# Control.net
KiCad netlist of a schematic drawn in Altium Designer
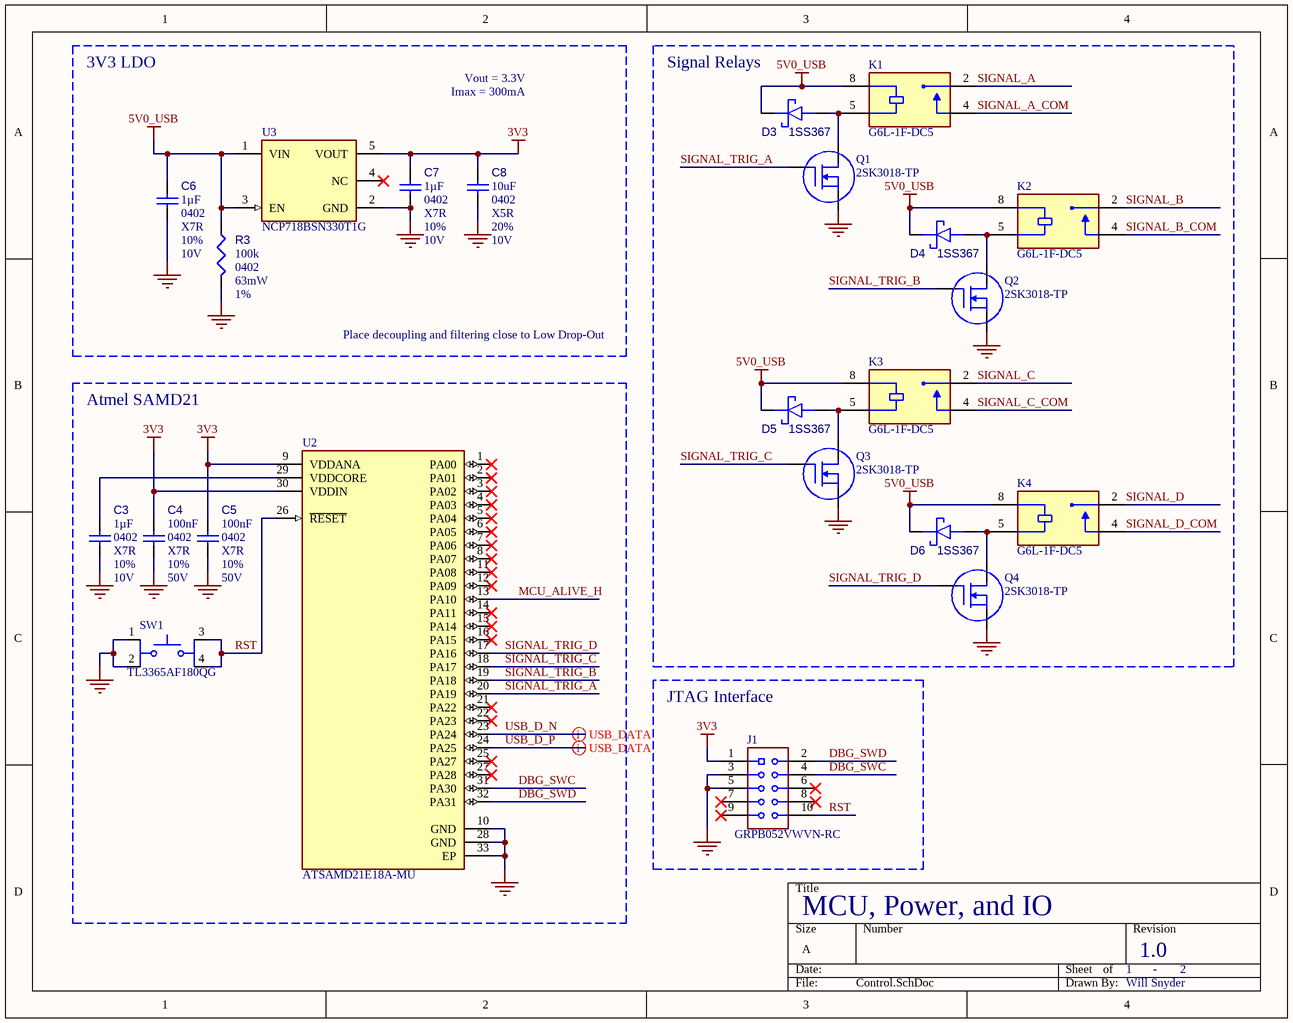
[diagram p0: Control.SchDoc]

(export (version "E")
  (design (tool "Eeschema 10.0.6"))
  (components
    (comp (ref "C3")
      (value "1µF")
      (footprint "CAPC1005X55X30NL05T10")
      (fields
        (field (name "CASE/PACKAGE") "0402")
        (field (name "VOLTAGE RATING") "10V")
        (field (name "CAPACITOR TYPE") "X7R")
        (field (name "TOLERANCE") "10%")
        (field (name "Comment") "GRM155Z71A105KE01D")
      )
      (libsource (lib "Personal Workspace") (part "CAP-NP-2"))
    )
    (comp (ref "C4")
      (value "100nF")
      (footprint "CAPC1005X55X30NL05T10")
      (fields
        (field (name "VOLTAGE RATING") "50V")
        (field (name "CAPACITOR TYPE") "X7R")
        (field (name "CASE/PACKAGE") "0402")
        (field (name "TOLERANCE") "10%")
        (field (name "Comment") "04025C104KAT4A")
      )
      (libsource (lib "Personal Workspace") (part "CAP-NP-2"))
    )
    (comp (ref "C5")
      (value "100nF")
      (footprint "CAPC1005X55X30NL05T10")
      (fields
        (field (name "VOLTAGE RATING") "50V")
        (field (name "CAPACITOR TYPE") "X7R")
        (field (name "CASE/PACKAGE") "0402")
        (field (name "TOLERANCE") "10%")
        (field (name "Comment") "04025C104KAT4A")
      )
      (libsource (lib "Personal Workspace") (part "CAP-NP-2"))
    )
    (comp (ref "C6")
      (value "1µF")
      (footprint "CAPC1005X55X30NL05T10")
      (fields
        (field (name "CASE/PACKAGE") "0402")
        (field (name "VOLTAGE RATING") "10V")
        (field (name "CAPACITOR TYPE") "X7R")
        (field (name "TOLERANCE") "10%")
        (field (name "Comment") "GRM155Z71A105KE01D")
      )
      (libsource (lib "Personal Workspace") (part "CAP-NP-2"))
    )
    (comp (ref "C7")
      (value "1µF")
      (footprint "CAPC1005X55X30NL05T10")
      (fields
        (field (name "CASE/PACKAGE") "0402")
        (field (name "VOLTAGE RATING") "10V")
        (field (name "CAPACITOR TYPE") "X7R")
        (field (name "TOLERANCE") "10%")
        (field (name "Comment") "GRM155Z71A105KE01D")
      )
      (libsource (lib "Personal Workspace") (part "CAP-NP-2"))
    )
    (comp (ref "C8")
      (value "10uF")
      (footprint "CAPC1005X55X30NL05T10")
      (fields
        (field (name "CAPACITOR TYPE") "X5R")
        (field (name "VOLTAGE RATING") "10V")
        (field (name "TOLERANCE") "20%")
        (field (name "CASE/PACKAGE") "0402")
        (field (name "Comment") "GRM155R61A106ME11J")
      )
      (libsource (lib "Personal Workspace") (part "CAP-NP-2"))
    )
    (comp (ref "D3")
      (value "1SS367")
      (footprint "SOD2513X114N")
      (description "Diode Schottky 10V 100mA USC")
      (libsource (lib "Personal Workspace") (part "1SS367"))
    )
    (comp (ref "D4")
      (value "1SS367")
      (footprint "SOD2513X114N")
      (description "Diode Schottky 10V 100mA USC")
      (libsource (lib "Personal Workspace") (part "1SS367"))
    )
    (comp (ref "D5")
      (value "1SS367")
      (footprint "SOD2513X114N")
      (description "Diode Schottky 10V 100mA USC")
      (libsource (lib "Personal Workspace") (part "1SS367"))
    )
    (comp (ref "D6")
      (value "1SS367")
      (footprint "SOD2513X114N")
      (description "Diode Schottky 10V 100mA USC")
      (libsource (lib "Personal Workspace") (part "1SS367"))
    )
    (comp (ref "J1")
      (value "GRPB052VWVN-RC")
      (footprint "SULLINS_GRPB052VWVN-RC")
      (description "Connector Header Through Hole 10 position 0.050 (1.27mm)")
      (fields (field (name "MF") "Sullins"))
      (libsource (lib "Personal Workspace") (part "GRPB052VWVN-RC"))
    )
    (comp (ref "K1")
      (value "G6L-1F-DC5")
      (footprint "RELAY_G6L-1F-DC5")
      (description "Telecom Relay SPST-NO (1 Form A) Surface Mount")
      (fields (field (name "MP") "G6L-1F-TR-DC5") (field (name "MF") "Omron Electronics"))
      (libsource (lib "Personal Workspace") (part "G6L-1F-DC5"))
    )
    (comp (ref "K2")
      (value "G6L-1F-DC5")
      (footprint "RELAY_G6L-1F-DC5")
      (description "Telecom Relay SPST-NO (1 Form A) Surface Mount")
      (fields (field (name "MP") "G6L-1F-TR-DC5") (field (name "MF") "Omron Electronics"))
      (libsource (lib "Personal Workspace") (part "G6L-1F-DC5"))
    )
    (comp (ref "K3")
      (value "G6L-1F-DC5")
      (footprint "RELAY_G6L-1F-DC5")
      (description "Telecom Relay SPST-NO (1 Form A) Surface Mount")
      (fields (field (name "MP") "G6L-1F-TR-DC5") (field (name "MF") "Omron Electronics"))
      (libsource (lib "Personal Workspace") (part "G6L-1F-DC5"))
    )
    (comp (ref "K4")
      (value "G6L-1F-DC5")
      (footprint "RELAY_G6L-1F-DC5")
      (description "Telecom Relay SPST-NO (1 Form A) Surface Mount")
      (fields (field (name "MP") "G6L-1F-TR-DC5") (field (name "MF") "Omron Electronics"))
      (libsource (lib "Personal Workspace") (part "G6L-1F-DC5"))
    )
    (comp (ref "Q1")
      (value "2SK3018-TP")
      (footprint "2SK3018-TP-Footprint-1")
      (description "Mosfet, N-Ch, 30V, 0.1A, Sot-323 Rohs Compliant: Yes")
      (libsource (lib "Personal Workspace") (part "2SK3018-TP"))
    )
    (comp (ref "Q2")
      (value "2SK3018-TP")
      (footprint "2SK3018-TP-Footprint-1")
      (description "Mosfet, N-Ch, 30V, 0.1A, Sot-323 Rohs Compliant: Yes")
      (libsource (lib "Personal Workspace") (part "2SK3018-TP"))
    )
    (comp (ref "Q3")
      (value "2SK3018-TP")
      (footprint "2SK3018-TP-Footprint-1")
      (description "Mosfet, N-Ch, 30V, 0.1A, Sot-323 Rohs Compliant: Yes")
      (libsource (lib "Personal Workspace") (part "2SK3018-TP"))
    )
    (comp (ref "Q4")
      (value "2SK3018-TP")
      (footprint "2SK3018-TP-Footprint-1")
      (description "Mosfet, N-Ch, 30V, 0.1A, Sot-323 Rohs Compliant: Yes")
      (libsource (lib "Personal Workspace") (part "2SK3018-TP"))
    )
    (comp (ref "R3")
      (value "100k")
      (footprint "RESC0402(1005)_L")
      (description "100K 0.063W 1% 0402 (1005 Metric)  SMD")
      (fields
        (field (name "POWER") "63mW")
        (field (name "CASE/PACKAGE") "0402")
        (field (name "TOLERANCE") "1%")
        (field (name "Comment") "100KR2F")
      )
      (libsource (lib "Personal Workspace") (part "100KR2F"))
    )
    (comp (ref "SW1")
      (value "TL3365AF180QG")
      (footprint "SW_TL3365AF180QG")
      (description "Tactile Switch SPST-NO Top Actuated Surface Mount")
      (fields (field (name "MF") "E-Switch"))
      (libsource (lib "Personal Workspace") (part "TL3365AF180QG"))
    )
    (comp (ref "U2")
      (value "ATSAMD21E18A-MU")
      (footprint "FP-PG-IPC_A")
      (description "RISC Microcontroller, 32-Bit, FLASH, CORTEX-M0 CPU, 48MHz, CMOS")
      (libsource (lib "Personal Workspace") (part "079772c84f40789a0aafecd75ebb365"))
    )
    (comp (ref "U3")
      (value "NCP718BSN330T1G")
      (footprint "SOT95P280X100-5N")
      (description "Fixed Positive LDO Regulator, 3.3V, 440V Dropout, PDSO5")
      (libsource (lib "Personal Workspace") (part "96048095611b4a9579e1e315950d302"))
    )
  )
  (nets
    (net (code "1") (name "/DBG_SWC") (class "Default")
      (node (ref "J1") (pin "4") (pinfunction "4_4") (pintype "passive"))
      (node (ref "U2") (pin "31") (pinfunction "PA30_31") (pintype "bidirectional"))
    )
    (net (code "2") (name "/DBG_SWD") (class "Default")
      (node (ref "J1") (pin "2") (pinfunction "2_2") (pintype "passive"))
      (node (ref "U2") (pin "32") (pinfunction "PA31_32") (pintype "bidirectional"))
    )
    (net (code "3") (name "/MCU_ALIVE_H") (class "Default")
      (node (ref "U2") (pin "13") (pinfunction "PA10_13") (pintype "bidirectional"))
    )
    (net (code "4") (name "/RST") (class "Default")
      (node (ref "J1") (pin "10") (pinfunction "10_10") (pintype "passive"))
      (node (ref "SW1") (pin "3") (pinfunction "3_3") (pintype "passive"))
      (node (ref "SW1") (pin "4") (pinfunction "4_4") (pintype "passive"))
      (node (ref "U2") (pin "26") (pinfunction "~{RESET}_26") (pintype "input"))
    )
    (net (code "5") (name "/SIGNAL_A") (class "Default")
      (node (ref "K1") (pin "2") (pinfunction "COM_2") (pintype "passive"))
    )
    (net (code "6") (name "/SIGNAL_A_COM") (class "Default")
      (node (ref "K1") (pin "4") (pinfunction "NO_4") (pintype "passive"))
    )
    (net (code "7") (name "/SIGNAL_B") (class "Default")
      (node (ref "K2") (pin "2") (pinfunction "COM_2") (pintype "passive"))
    )
    (net (code "8") (name "/SIGNAL_B_COM") (class "Default")
      (node (ref "K2") (pin "4") (pinfunction "NO_4") (pintype "passive"))
    )
    (net (code "9") (name "/SIGNAL_C") (class "Default")
      (node (ref "K3") (pin "2") (pinfunction "COM_2") (pintype "passive"))
    )
    (net (code "10") (name "/SIGNAL_C_COM") (class "Default")
      (node (ref "K3") (pin "4") (pinfunction "NO_4") (pintype "passive"))
    )
    (net (code "11") (name "/SIGNAL_D") (class "Default")
      (node (ref "K4") (pin "2") (pinfunction "COM_2") (pintype "passive"))
    )
    (net (code "12") (name "/SIGNAL_D_COM") (class "Default")
      (node (ref "K4") (pin "4") (pinfunction "NO_4") (pintype "passive"))
    )
    (net (code "13") (name "/SIGNAL_TRIG_A") (class "Default")
      (node (ref "Q1") (pin "1") (pinfunction "G_1") (pintype "passive"))
      (node (ref "U2") (pin "20") (pinfunction "PA19_20") (pintype "bidirectional"))
    )
    (net (code "14") (name "/SIGNAL_TRIG_B") (class "Default")
      (node (ref "Q2") (pin "1") (pinfunction "G_1") (pintype "passive"))
      (node (ref "U2") (pin "19") (pinfunction "PA18_19") (pintype "bidirectional"))
    )
    (net (code "15") (name "/SIGNAL_TRIG_C") (class "Default")
      (node (ref "Q3") (pin "1") (pinfunction "G_1") (pintype "passive"))
      (node (ref "U2") (pin "18") (pinfunction "PA17_18") (pintype "bidirectional"))
    )
    (net (code "16") (name "/SIGNAL_TRIG_D") (class "Default")
      (node (ref "Q4") (pin "1") (pinfunction "G_1") (pintype "passive"))
      (node (ref "U2") (pin "17") (pinfunction "PA16_17") (pintype "bidirectional"))
    )
    (net (code "17") (name "/USB_D_N") (class "Default")
      (node (ref "U2") (pin "23") (pinfunction "PA24_23") (pintype "bidirectional"))
    )
    (net (code "18") (name "/USB_D_P") (class "Default")
      (node (ref "U2") (pin "24") (pinfunction "PA25_24") (pintype "bidirectional"))
    )
    (net (code "19") (name "3V3") (class "Default")
      (node (ref "C4") (pin "1") (pinfunction "1_1") (pintype "passive"))
      (node (ref "C5") (pin "1") (pinfunction "1_1") (pintype "passive"))
      (node (ref "C7") (pin "1") (pinfunction "1_1") (pintype "passive"))
      (node (ref "C8") (pin "1") (pinfunction "1_1") (pintype "passive"))
      (node (ref "J1") (pin "1") (pinfunction "1_1") (pintype "passive"))
      (node (ref "U2") (pin "30") (pinfunction "VDDIN_30") (pintype "power_in"))
      (node (ref "U2") (pin "9") (pinfunction "VDDANA_9") (pintype "power_in"))
      (node (ref "U3") (pin "5") (pinfunction "VOUT_5") (pintype "power_in"))
    )
    (net (code "20") (name "5V0_USB") (class "Default")
      (node (ref "C6") (pin "1") (pinfunction "1_1") (pintype "passive"))
      (node (ref "D3") (pin "1") (pinfunction "K_1") (pintype "passive"))
      (node (ref "D4") (pin "1") (pinfunction "K_1") (pintype "passive"))
      (node (ref "D5") (pin "1") (pinfunction "K_1") (pintype "passive"))
      (node (ref "D6") (pin "1") (pinfunction "K_1") (pintype "passive"))
      (node (ref "K1") (pin "8") (pinfunction "COIL1_8") (pintype "passive"))
      (node (ref "K2") (pin "8") (pinfunction "COIL1_8") (pintype "passive"))
      (node (ref "K3") (pin "8") (pinfunction "COIL1_8") (pintype "passive"))
      (node (ref "K4") (pin "8") (pinfunction "COIL1_8") (pintype "passive"))
      (node (ref "R3") (pin "1") (pinfunction "1_1") (pintype "passive"))
      (node (ref "U3") (pin "1") (pinfunction "VIN_1") (pintype "power_in"))
      (node (ref "U3") (pin "3") (pinfunction "EN_3") (pintype "input"))
    )
    (net (code "21") (name "GND") (class "Default")
      (node (ref "C3") (pin "2") (pinfunction "2_2") (pintype "passive"))
      (node (ref "C4") (pin "2") (pinfunction "2_2") (pintype "passive"))
      (node (ref "C5") (pin "2") (pinfunction "2_2") (pintype "passive"))
      (node (ref "C6") (pin "2") (pinfunction "2_2") (pintype "passive"))
      (node (ref "C7") (pin "2") (pinfunction "2_2") (pintype "passive"))
      (node (ref "C8") (pin "2") (pinfunction "2_2") (pintype "passive"))
      (node (ref "J1") (pin "3") (pinfunction "3_3") (pintype "passive"))
      (node (ref "J1") (pin "5") (pinfunction "5_5") (pintype "passive"))
      (node (ref "Q1") (pin "2") (pinfunction "S_2") (pintype "passive"))
      (node (ref "Q2") (pin "2") (pinfunction "S_2") (pintype "passive"))
      (node (ref "Q3") (pin "2") (pinfunction "S_2") (pintype "passive"))
      (node (ref "Q4") (pin "2") (pinfunction "S_2") (pintype "passive"))
      (node (ref "R3") (pin "2") (pinfunction "2_2") (pintype "passive"))
      (node (ref "SW1") (pin "1") (pinfunction "1_1") (pintype "passive"))
      (node (ref "SW1") (pin "2") (pinfunction "2_2") (pintype "passive"))
      (node (ref "U2") (pin "10") (pinfunction "GND_10") (pintype "power_in"))
      (node (ref "U2") (pin "28") (pinfunction "GND_28") (pintype "power_in"))
      (node (ref "U2") (pin "33") (pinfunction "EP_33") (pintype "power_in"))
      (node (ref "U3") (pin "2") (pinfunction "GND_2") (pintype "power_in"))
    )
    (net (code "22") (name "Net-(D3-A)") (class "Default")
      (node (ref "D3") (pin "2") (pinfunction "A_2") (pintype "passive"))
      (node (ref "K1") (pin "5") (pinfunction "COIL2_5") (pintype "passive"))
      (node (ref "Q1") (pin "3") (pinfunction "D_3") (pintype "passive"))
    )
    (net (code "23") (name "Net-(D4-A)") (class "Default")
      (node (ref "D4") (pin "2") (pinfunction "A_2") (pintype "passive"))
      (node (ref "K2") (pin "5") (pinfunction "COIL2_5") (pintype "passive"))
      (node (ref "Q2") (pin "3") (pinfunction "D_3") (pintype "passive"))
    )
    (net (code "24") (name "Net-(D5-A)") (class "Default")
      (node (ref "D5") (pin "2") (pinfunction "A_2") (pintype "passive"))
      (node (ref "K3") (pin "5") (pinfunction "COIL2_5") (pintype "passive"))
      (node (ref "Q3") (pin "3") (pinfunction "D_3") (pintype "passive"))
    )
    (net (code "25") (name "Net-(D6-A)") (class "Default")
      (node (ref "D6") (pin "2") (pinfunction "A_2") (pintype "passive"))
      (node (ref "K4") (pin "5") (pinfunction "COIL2_5") (pintype "passive"))
      (node (ref "Q4") (pin "3") (pinfunction "D_3") (pintype "passive"))
    )
    (net (code "26") (name "Net-(U2-VDDCORE)") (class "Default")
      (node (ref "C3") (pin "1") (pinfunction "1_1") (pintype "passive"))
      (node (ref "U2") (pin "29") (pinfunction "VDDCORE_29") (pintype "power_in"))
    )
    (net (code "27") (name "unconnected-(J1-Pad6)") (class "Default")
      (node (ref "J1") (pin "6") (pinfunction "6_6") (pintype "passive+no_connect"))
    )
    (net (code "28") (name "unconnected-(J1-Pad7)") (class "Default")
      (node (ref "J1") (pin "7") (pinfunction "7_7") (pintype "passive+no_connect"))
    )
    (net (code "29") (name "unconnected-(J1-Pad8)") (class "Default")
      (node (ref "J1") (pin "8") (pinfunction "8_8") (pintype "passive+no_connect"))
    )
    (net (code "30") (name "unconnected-(J1-Pad9)") (class "Default")
      (node (ref "J1") (pin "9") (pinfunction "9_9") (pintype "passive+no_connect"))
    )
    (net (code "31") (name "unconnected-(U2-PA00-Pad1)") (class "Default")
      (node (ref "U2") (pin "1") (pinfunction "PA00_1") (pintype "bidirectional+no_connect"))
    )
    (net (code "32") (name "unconnected-(U2-PA01-Pad2)") (class "Default")
      (node (ref "U2") (pin "2") (pinfunction "PA01_2") (pintype "bidirectional+no_connect"))
    )
    (net (code "33") (name "unconnected-(U2-PA02-Pad3)") (class "Default")
      (node (ref "U2") (pin "3") (pinfunction "PA02_3") (pintype "bidirectional+no_connect"))
    )
    (net (code "34") (name "unconnected-(U2-PA03-Pad4)") (class "Default")
      (node (ref "U2") (pin "4") (pinfunction "PA03_4") (pintype "bidirectional+no_connect"))
    )
    (net (code "35") (name "unconnected-(U2-PA04-Pad5)") (class "Default")
      (node (ref "U2") (pin "5") (pinfunction "PA04_5") (pintype "bidirectional+no_connect"))
    )
    (net (code "36") (name "unconnected-(U2-PA05-Pad6)") (class "Default")
      (node (ref "U2") (pin "6") (pinfunction "PA05_6") (pintype "bidirectional+no_connect"))
    )
    (net (code "37") (name "unconnected-(U2-PA06-Pad7)") (class "Default")
      (node (ref "U2") (pin "7") (pinfunction "PA06_7") (pintype "bidirectional+no_connect"))
    )
    (net (code "38") (name "unconnected-(U2-PA07-Pad8)") (class "Default")
      (node (ref "U2") (pin "8") (pinfunction "PA07_8") (pintype "bidirectional+no_connect"))
    )
    (net (code "39") (name "unconnected-(U2-PA08-Pad11)") (class "Default")
      (node (ref "U2") (pin "11") (pinfunction "PA08_11") (pintype "bidirectional+no_connect"))
    )
    (net (code "40") (name "unconnected-(U2-PA09-Pad12)") (class "Default")
      (node (ref "U2") (pin "12") (pinfunction "PA09_12") (pintype "bidirectional+no_connect"))
    )
    (net (code "41") (name "unconnected-(U2-PA11-Pad14)") (class "Default")
      (node (ref "U2") (pin "14") (pinfunction "PA11_14") (pintype "bidirectional+no_connect"))
    )
    (net (code "42") (name "unconnected-(U2-PA14-Pad15)") (class "Default")
      (node (ref "U2") (pin "15") (pinfunction "PA14_15") (pintype "bidirectional+no_connect"))
    )
    (net (code "43") (name "unconnected-(U2-PA15-Pad16)") (class "Default")
      (node (ref "U2") (pin "16") (pinfunction "PA15_16") (pintype "bidirectional+no_connect"))
    )
    (net (code "44") (name "unconnected-(U2-PA22-Pad21)") (class "Default")
      (node (ref "U2") (pin "21") (pinfunction "PA22_21") (pintype "bidirectional+no_connect"))
    )
    (net (code "45") (name "unconnected-(U2-PA23-Pad22)") (class "Default")
      (node (ref "U2") (pin "22") (pinfunction "PA23_22") (pintype "bidirectional+no_connect"))
    )
    (net (code "46") (name "unconnected-(U2-PA27-Pad25)") (class "Default")
      (node (ref "U2") (pin "25") (pinfunction "PA27_25") (pintype "bidirectional+no_connect"))
    )
    (net (code "47") (name "unconnected-(U2-PA28-Pad27)") (class "Default")
      (node (ref "U2") (pin "27") (pinfunction "PA28_27") (pintype "bidirectional+no_connect"))
    )
    (net (code "48") (name "unconnected-(U3-NC-Pad4)") (class "Default")
      (node (ref "U3") (pin "4") (pinfunction "NC_4") (pintype "passive+no_connect"))
    )
  )
)
